# vis-analog-out.net
KiCad netlist of a schematic drawn in EAGLE
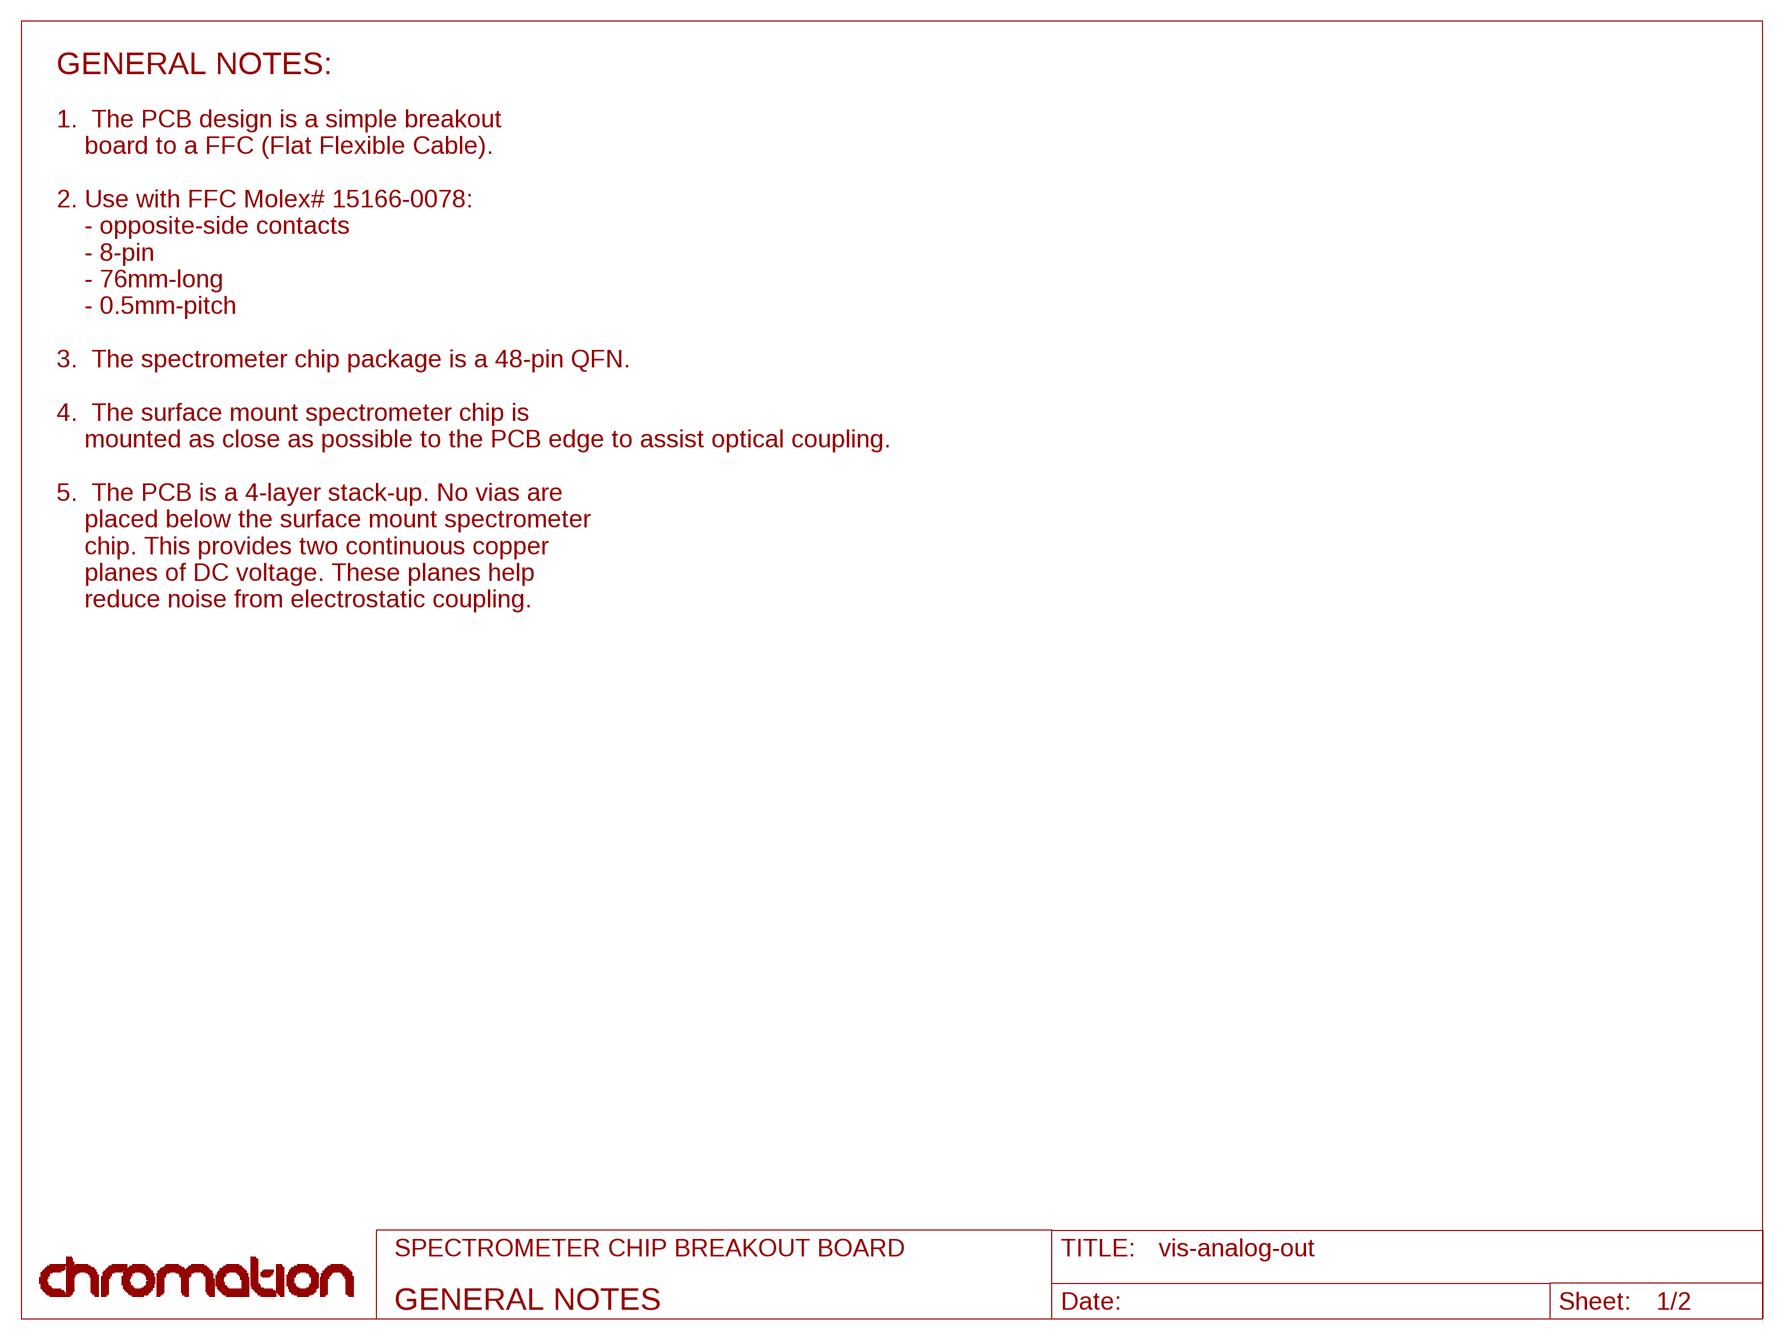
[diagram p0: schematic, sheet 1]
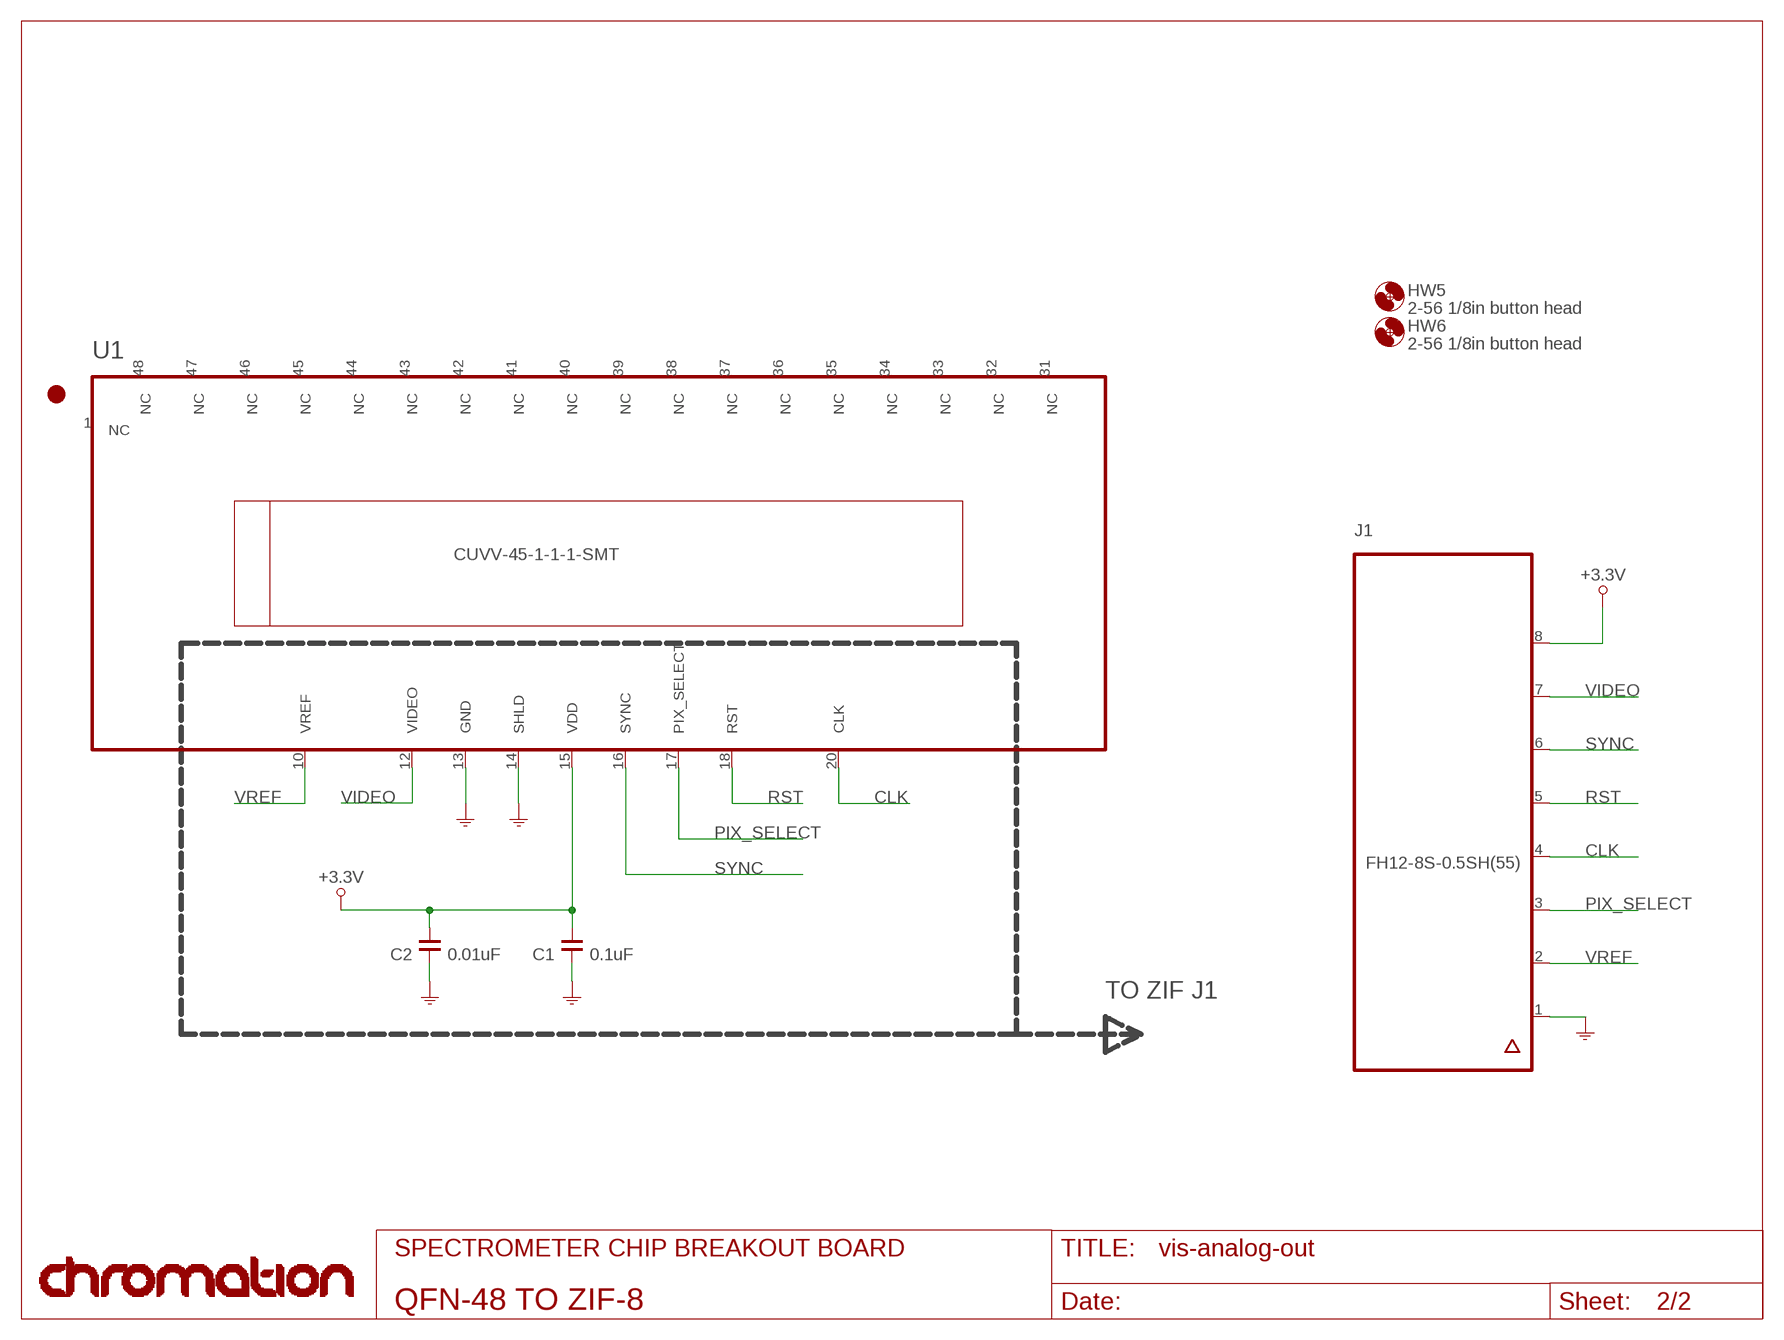
[diagram p1: schematic, sheet 2]

(export (version "E")
  (design (tool "Eeschema 10.0.6"))
  (components
    (comp (ref "C1")
      (value "0.1uF")
      (footprint "eagle-import:0603")
      (libsource (lib "eagle-import") (part "C_0603"))
    )
    (comp (ref "C2")
      (value "0.01uF")
      (footprint "eagle-import:0603")
      (libsource (lib "eagle-import") (part "C_0603"))
    )
    (comp (ref "HW5")
      (value "2-56 1/8in button head")
      (footprint "eagle-import:MCMASTER_92949A081")
      (libsource (lib "eagle-import") (part "MOUNTING-HOLE_2-56_SCREW"))
    )
    (comp (ref "HW6")
      (value "2-56 1/8in button head")
      (footprint "eagle-import:MCMASTER_92949A081")
      (libsource (lib "eagle-import") (part "MOUNTING-HOLE_2-56_SCREW"))
    )
    (comp (ref "J1")
      (value "FH12-8S-0.5SH(55)")
      (footprint "eagle-import:FH12-8S-0.5SH")
      (libsource (lib "eagle-import") (part "ZIF_8-PIN"))
    )
    (comp (ref "U1")
      (value "CUVV-45-1-1-1-SMT")
      (footprint "eagle-import:VIS-PKG")
      (libsource (lib "eagle-import") (part "VIS-QFN48"))
    )
  )
  (nets
    (net (code "1") (name "+3.3V") (class "Default")
      (node (ref "C1") (pin "1") (pinfunction "1_1") (pintype "passive"))
      (node (ref "C2") (pin "1") (pinfunction "1_1") (pintype "passive"))
      (node (ref "J1") (pin "8") (pinfunction "8_8") (pintype "bidirectional"))
      (node (ref "U1") (pin "15") (pinfunction "VDD_15") (pintype "bidirectional"))
    )
    (net (code "2") (name "CLK") (class "Default")
      (node (ref "J1") (pin "4") (pinfunction "4_4") (pintype "bidirectional"))
      (node (ref "U1") (pin "20") (pinfunction "CLK_20") (pintype "bidirectional"))
    )
    (net (code "3") (name "GND") (class "Default")
      (node (ref "C1") (pin "2") (pinfunction "2_2") (pintype "passive"))
      (node (ref "C2") (pin "2") (pinfunction "2_2") (pintype "passive"))
      (node (ref "J1") (pin "1") (pinfunction "1_1") (pintype "bidirectional"))
      (node (ref "U1") (pin "13") (pinfunction "GND_13") (pintype "bidirectional"))
      (node (ref "U1") (pin "14") (pinfunction "SHLD_14") (pintype "bidirectional"))
    )
    (net (code "4") (name "PIX_SELECT") (class "Default")
      (node (ref "J1") (pin "3") (pinfunction "3_3") (pintype "bidirectional"))
      (node (ref "U1") (pin "17") (pinfunction "PIX_SELECT_17") (pintype "bidirectional"))
    )
    (net (code "5") (name "RST") (class "Default")
      (node (ref "J1") (pin "5") (pinfunction "5_5") (pintype "bidirectional"))
      (node (ref "U1") (pin "18") (pinfunction "RST_18") (pintype "bidirectional"))
    )
    (net (code "6") (name "SYNC") (class "Default")
      (node (ref "J1") (pin "6") (pinfunction "6_6") (pintype "bidirectional"))
      (node (ref "U1") (pin "16") (pinfunction "SYNC_16") (pintype "bidirectional"))
    )
    (net (code "7") (name "VIDEO") (class "Default")
      (node (ref "J1") (pin "7") (pinfunction "7_7") (pintype "bidirectional"))
      (node (ref "U1") (pin "12") (pinfunction "VIDEO_12") (pintype "bidirectional"))
    )
    (net (code "8") (name "VREF") (class "Default")
      (node (ref "J1") (pin "2") (pinfunction "2_2") (pintype "bidirectional"))
      (node (ref "U1") (pin "10") (pinfunction "VREF_10") (pintype "bidirectional"))
    )
    (net (code "9") (name "unconnected-(J1-LEG-PadLEG@1)") (class "Default")
      (node (ref "J1") (pin "LEG@1") (pinfunction "LEG_LEG@1") (pintype "no_connect"))
    )
    (net (code "10") (name "unconnected-(J1-LEG-PadLEG@2)") (class "Default")
      (node (ref "J1") (pin "LEG@2") (pinfunction "LEG_LEG@2") (pintype "no_connect"))
    )
    (net (code "11") (name "unconnected-(U1-NC-Pad1)") (class "Default")
      (node (ref "U1") (pin "1") (pinfunction "NC_1") (pintype "no_connect"))
    )
    (net (code "12") (name "unconnected-(U1-NC-Pad2)") (class "Default")
      (node (ref "U1") (pin "2") (pinfunction "NC_2") (pintype "no_connect"))
    )
    (net (code "13") (name "unconnected-(U1-NC-Pad3)") (class "Default")
      (node (ref "U1") (pin "3") (pinfunction "NC_3") (pintype "no_connect"))
    )
    (net (code "14") (name "unconnected-(U1-NC-Pad4)") (class "Default")
      (node (ref "U1") (pin "4") (pinfunction "NC_4") (pintype "no_connect"))
    )
    (net (code "15") (name "unconnected-(U1-NC-Pad5)") (class "Default")
      (node (ref "U1") (pin "5") (pinfunction "NC_5") (pintype "no_connect"))
    )
    (net (code "16") (name "unconnected-(U1-NC-Pad6)") (class "Default")
      (node (ref "U1") (pin "6") (pinfunction "NC_6") (pintype "no_connect"))
    )
    (net (code "17") (name "unconnected-(U1-NC-Pad7)") (class "Default")
      (node (ref "U1") (pin "7") (pinfunction "NC_7") (pintype "no_connect"))
    )
    (net (code "18") (name "unconnected-(U1-NC-Pad8)") (class "Default")
      (node (ref "U1") (pin "8") (pinfunction "NC_8") (pintype "no_connect"))
    )
    (net (code "19") (name "unconnected-(U1-NC-Pad9)") (class "Default")
      (node (ref "U1") (pin "9") (pinfunction "NC_9") (pintype "no_connect"))
    )
    (net (code "20") (name "unconnected-(U1-NC-Pad11)") (class "Default")
      (node (ref "U1") (pin "11") (pinfunction "NC_11") (pintype "no_connect"))
    )
    (net (code "21") (name "unconnected-(U1-NC-Pad19)") (class "Default")
      (node (ref "U1") (pin "19") (pinfunction "NC_19") (pintype "no_connect"))
    )
    (net (code "22") (name "unconnected-(U1-NC-Pad21)") (class "Default")
      (node (ref "U1") (pin "21") (pinfunction "NC_21") (pintype "no_connect"))
    )
    (net (code "23") (name "unconnected-(U1-NC-Pad22)") (class "Default")
      (node (ref "U1") (pin "22") (pinfunction "NC_22") (pintype "no_connect"))
    )
    (net (code "24") (name "unconnected-(U1-NC-Pad23)") (class "Default")
      (node (ref "U1") (pin "23") (pinfunction "NC_23") (pintype "no_connect"))
    )
    (net (code "25") (name "unconnected-(U1-NC-Pad24)") (class "Default")
      (node (ref "U1") (pin "24") (pinfunction "NC_24") (pintype "no_connect"))
    )
    (net (code "26") (name "unconnected-(U1-NC-Pad25)") (class "Default")
      (node (ref "U1") (pin "25") (pinfunction "NC_25") (pintype "no_connect"))
    )
    (net (code "27") (name "unconnected-(U1-NC-Pad26)") (class "Default")
      (node (ref "U1") (pin "26") (pinfunction "NC_26") (pintype "no_connect"))
    )
    (net (code "28") (name "unconnected-(U1-NC-Pad27)") (class "Default")
      (node (ref "U1") (pin "27") (pinfunction "NC_27") (pintype "no_connect"))
    )
    (net (code "29") (name "unconnected-(U1-NC-Pad28)") (class "Default")
      (node (ref "U1") (pin "28") (pinfunction "NC_28") (pintype "no_connect"))
    )
    (net (code "30") (name "unconnected-(U1-NC-Pad29)") (class "Default")
      (node (ref "U1") (pin "29") (pinfunction "NC_29") (pintype "no_connect"))
    )
    (net (code "31") (name "unconnected-(U1-NC-Pad30)") (class "Default")
      (node (ref "U1") (pin "30") (pinfunction "NC_30") (pintype "no_connect"))
    )
    (net (code "32") (name "unconnected-(U1-NC-Pad31)") (class "Default")
      (node (ref "U1") (pin "31") (pinfunction "NC_31") (pintype "no_connect"))
    )
    (net (code "33") (name "unconnected-(U1-NC-Pad32)") (class "Default")
      (node (ref "U1") (pin "32") (pinfunction "NC_32") (pintype "no_connect"))
    )
    (net (code "34") (name "unconnected-(U1-NC-Pad33)") (class "Default")
      (node (ref "U1") (pin "33") (pinfunction "NC_33") (pintype "no_connect"))
    )
    (net (code "35") (name "unconnected-(U1-NC-Pad34)") (class "Default")
      (node (ref "U1") (pin "34") (pinfunction "NC_34") (pintype "no_connect"))
    )
    (net (code "36") (name "unconnected-(U1-NC-Pad35)") (class "Default")
      (node (ref "U1") (pin "35") (pinfunction "NC_35") (pintype "no_connect"))
    )
    (net (code "37") (name "unconnected-(U1-NC-Pad36)") (class "Default")
      (node (ref "U1") (pin "36") (pinfunction "NC_36") (pintype "no_connect"))
    )
    (net (code "38") (name "unconnected-(U1-NC-Pad37)") (class "Default")
      (node (ref "U1") (pin "37") (pinfunction "NC_37") (pintype "no_connect"))
    )
    (net (code "39") (name "unconnected-(U1-NC-Pad38)") (class "Default")
      (node (ref "U1") (pin "38") (pinfunction "NC_38") (pintype "no_connect"))
    )
    (net (code "40") (name "unconnected-(U1-NC-Pad39)") (class "Default")
      (node (ref "U1") (pin "39") (pinfunction "NC_39") (pintype "no_connect"))
    )
    (net (code "41") (name "unconnected-(U1-NC-Pad40)") (class "Default")
      (node (ref "U1") (pin "40") (pinfunction "NC_40") (pintype "no_connect"))
    )
    (net (code "42") (name "unconnected-(U1-NC-Pad41)") (class "Default")
      (node (ref "U1") (pin "41") (pinfunction "NC_41") (pintype "no_connect"))
    )
    (net (code "43") (name "unconnected-(U1-NC-Pad42)") (class "Default")
      (node (ref "U1") (pin "42") (pinfunction "NC_42") (pintype "no_connect"))
    )
    (net (code "44") (name "unconnected-(U1-NC-Pad43)") (class "Default")
      (node (ref "U1") (pin "43") (pinfunction "NC_43") (pintype "no_connect"))
    )
    (net (code "45") (name "unconnected-(U1-NC-Pad44)") (class "Default")
      (node (ref "U1") (pin "44") (pinfunction "NC_44") (pintype "no_connect"))
    )
    (net (code "46") (name "unconnected-(U1-NC-Pad45)") (class "Default")
      (node (ref "U1") (pin "45") (pinfunction "NC_45") (pintype "no_connect"))
    )
    (net (code "47") (name "unconnected-(U1-NC-Pad46)") (class "Default")
      (node (ref "U1") (pin "46") (pinfunction "NC_46") (pintype "no_connect"))
    )
    (net (code "48") (name "unconnected-(U1-NC-Pad47)") (class "Default")
      (node (ref "U1") (pin "47") (pinfunction "NC_47") (pintype "no_connect"))
    )
    (net (code "49") (name "unconnected-(U1-NC-Pad48)") (class "Default")
      (node (ref "U1") (pin "48") (pinfunction "NC_48") (pintype "no_connect"))
    )
  )
)
